# Sheet2.net
KiCad netlist of a schematic drawn in Altium Designer
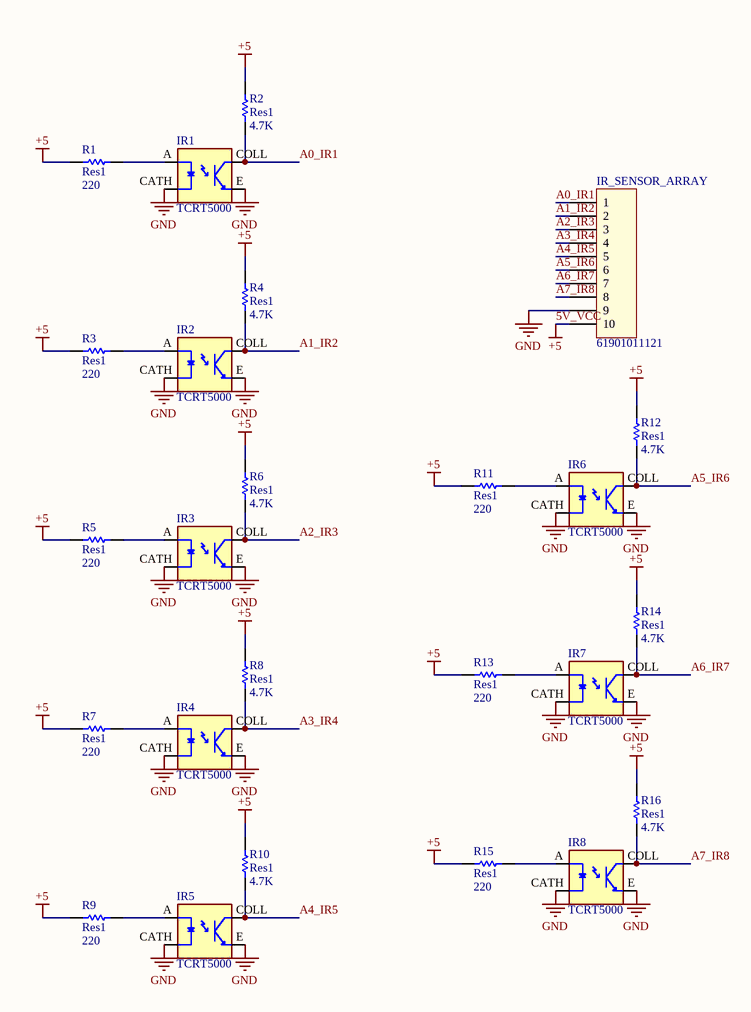
[diagram p0: Sheet2.SchDoc]

(export (version "E")
  (design (tool "Eeschema 10.0.6"))
  (components
    (comp (ref "IR1")
      (value "TCRT5000")
      (footprint "OPTO_TCRT5000")
      (description "950 nm 60 mA Through Hole Reflective Optical Sensor with Transistor Output")
      (libsource (lib "TCRT5000") (part "TCRT5000"))
    )
    (comp (ref "IR2")
      (value "TCRT5000")
      (footprint "OPTO_TCRT5000")
      (description "950 nm 60 mA Through Hole Reflective Optical Sensor with Transistor Output")
      (libsource (lib "TCRT5000") (part "TCRT5000"))
    )
    (comp (ref "IR3")
      (value "TCRT5000")
      (footprint "OPTO_TCRT5000")
      (description "950 nm 60 mA Through Hole Reflective Optical Sensor with Transistor Output")
      (libsource (lib "TCRT5000") (part "TCRT5000"))
    )
    (comp (ref "IR4")
      (value "TCRT5000")
      (footprint "OPTO_TCRT5000")
      (description "950 nm 60 mA Through Hole Reflective Optical Sensor with Transistor Output")
      (libsource (lib "TCRT5000") (part "TCRT5000"))
    )
    (comp (ref "IR5")
      (value "TCRT5000")
      (footprint "OPTO_TCRT5000")
      (description "950 nm 60 mA Through Hole Reflective Optical Sensor with Transistor Output")
      (libsource (lib "TCRT5000") (part "TCRT5000"))
    )
    (comp (ref "IR6")
      (value "TCRT5000")
      (footprint "OPTO_TCRT5000")
      (description "950 nm 60 mA Through Hole Reflective Optical Sensor with Transistor Output")
      (libsource (lib "TCRT5000") (part "TCRT5000"))
    )
    (comp (ref "IR7")
      (value "TCRT5000")
      (footprint "OPTO_TCRT5000")
      (description "950 nm 60 mA Through Hole Reflective Optical Sensor with Transistor Output")
      (libsource (lib "TCRT5000") (part "TCRT5000"))
    )
    (comp (ref "IR8")
      (value "TCRT5000")
      (footprint "OPTO_TCRT5000")
      (description "950 nm 60 mA Through Hole Reflective Optical Sensor with Transistor Output")
      (libsource (lib "TCRT5000") (part "TCRT5000"))
    )
    (comp (ref "IR_SENSOR_ARRAY")
      (value "61901011121")
      (footprint "61901011121")
      (description "WR-WTB 2.54mm Male Locking Header, 10p")
      (fields (field (name "PUBLISHER") "Wurth Elektronik"))
      (libsource (lib "Relimate") (part "61901011121"))
    )
    (comp (ref "R1")
      (value "Res1")
      (footprint "AXIAL-0.3")
      (description "Resistor")
      (fields (field (name "ALTIUM_VALUE") "220") (field (name "PUBLISHER") "Altium Limited"))
      (libsource (lib "Miscellaneous Devices") (part "Res1"))
    )
    (comp (ref "R2")
      (value "Res1")
      (footprint "AXIAL-0.3")
      (description "Resistor")
      (fields (field (name "ALTIUM_VALUE") "4.7K") (field (name "PUBLISHER") "Altium Limited"))
      (libsource (lib "Miscellaneous Devices") (part "Res1"))
    )
    (comp (ref "R3")
      (value "Res1")
      (footprint "AXIAL-0.3")
      (description "Resistor")
      (fields (field (name "ALTIUM_VALUE") "220") (field (name "PUBLISHER") "Altium Limited"))
      (libsource (lib "Miscellaneous Devices") (part "Res1"))
    )
    (comp (ref "R4")
      (value "Res1")
      (footprint "AXIAL-0.3")
      (description "Resistor")
      (fields (field (name "ALTIUM_VALUE") "4.7K") (field (name "PUBLISHER") "Altium Limited"))
      (libsource (lib "Miscellaneous Devices") (part "Res1"))
    )
    (comp (ref "R5")
      (value "Res1")
      (footprint "AXIAL-0.3")
      (description "Resistor")
      (fields (field (name "ALTIUM_VALUE") "220") (field (name "PUBLISHER") "Altium Limited"))
      (libsource (lib "Miscellaneous Devices") (part "Res1"))
    )
    (comp (ref "R6")
      (value "Res1")
      (footprint "AXIAL-0.3")
      (description "Resistor")
      (fields (field (name "ALTIUM_VALUE") "4.7K") (field (name "PUBLISHER") "Altium Limited"))
      (libsource (lib "Miscellaneous Devices") (part "Res1"))
    )
    (comp (ref "R7")
      (value "Res1")
      (footprint "AXIAL-0.3")
      (description "Resistor")
      (fields (field (name "ALTIUM_VALUE") "220") (field (name "PUBLISHER") "Altium Limited"))
      (libsource (lib "Miscellaneous Devices") (part "Res1"))
    )
    (comp (ref "R8")
      (value "Res1")
      (footprint "AXIAL-0.3")
      (description "Resistor")
      (fields (field (name "ALTIUM_VALUE") "4.7K") (field (name "PUBLISHER") "Altium Limited"))
      (libsource (lib "Miscellaneous Devices") (part "Res1"))
    )
    (comp (ref "R9")
      (value "Res1")
      (footprint "AXIAL-0.3")
      (description "Resistor")
      (fields (field (name "ALTIUM_VALUE") "220") (field (name "PUBLISHER") "Altium Limited"))
      (libsource (lib "Miscellaneous Devices") (part "Res1"))
    )
    (comp (ref "R10")
      (value "Res1")
      (footprint "AXIAL-0.3")
      (description "Resistor")
      (fields (field (name "ALTIUM_VALUE") "4.7K") (field (name "PUBLISHER") "Altium Limited"))
      (libsource (lib "Miscellaneous Devices") (part "Res1"))
    )
    (comp (ref "R11")
      (value "Res1")
      (footprint "AXIAL-0.3")
      (description "Resistor")
      (fields (field (name "ALTIUM_VALUE") "220") (field (name "PUBLISHER") "Altium Limited"))
      (libsource (lib "Miscellaneous Devices") (part "Res1"))
    )
    (comp (ref "R12")
      (value "Res1")
      (footprint "AXIAL-0.3")
      (description "Resistor")
      (fields (field (name "ALTIUM_VALUE") "4.7K") (field (name "PUBLISHER") "Altium Limited"))
      (libsource (lib "Miscellaneous Devices") (part "Res1"))
    )
    (comp (ref "R13")
      (value "Res1")
      (footprint "AXIAL-0.3")
      (description "Resistor")
      (fields (field (name "ALTIUM_VALUE") "220") (field (name "PUBLISHER") "Altium Limited"))
      (libsource (lib "Miscellaneous Devices") (part "Res1"))
    )
    (comp (ref "R14")
      (value "Res1")
      (footprint "AXIAL-0.3")
      (description "Resistor")
      (fields (field (name "ALTIUM_VALUE") "4.7K") (field (name "PUBLISHER") "Altium Limited"))
      (libsource (lib "Miscellaneous Devices") (part "Res1"))
    )
    (comp (ref "R15")
      (value "Res1")
      (footprint "AXIAL-0.3")
      (description "Resistor")
      (fields (field (name "ALTIUM_VALUE") "220") (field (name "PUBLISHER") "Altium Limited"))
      (libsource (lib "Miscellaneous Devices") (part "Res1"))
    )
    (comp (ref "R16")
      (value "Res1")
      (footprint "AXIAL-0.3")
      (description "Resistor")
      (fields (field (name "ALTIUM_VALUE") "4.7K") (field (name "PUBLISHER") "Altium Limited"))
      (libsource (lib "Miscellaneous Devices") (part "Res1"))
    )
  )
  (nets
    (net (code "1") (name "+5") (class "Default")
      (node (ref "IR_SENSOR_ARRAY") (pin "10") (pinfunction "10_10") (pintype "passive"))
      (node (ref "R1") (pin "1") (pinfunction "1_1") (pintype "passive"))
      (node (ref "R10") (pin "2") (pinfunction "2_2") (pintype "passive"))
      (node (ref "R11") (pin "1") (pinfunction "1_1") (pintype "passive"))
      (node (ref "R12") (pin "2") (pinfunction "2_2") (pintype "passive"))
      (node (ref "R13") (pin "1") (pinfunction "1_1") (pintype "passive"))
      (node (ref "R14") (pin "2") (pinfunction "2_2") (pintype "passive"))
      (node (ref "R15") (pin "1") (pinfunction "1_1") (pintype "passive"))
      (node (ref "R16") (pin "2") (pinfunction "2_2") (pintype "passive"))
      (node (ref "R2") (pin "2") (pinfunction "2_2") (pintype "passive"))
      (node (ref "R3") (pin "1") (pinfunction "1_1") (pintype "passive"))
      (node (ref "R4") (pin "2") (pinfunction "2_2") (pintype "passive"))
      (node (ref "R5") (pin "1") (pinfunction "1_1") (pintype "passive"))
      (node (ref "R6") (pin "2") (pinfunction "2_2") (pintype "passive"))
      (node (ref "R7") (pin "1") (pinfunction "1_1") (pintype "passive"))
      (node (ref "R8") (pin "2") (pinfunction "2_2") (pintype "passive"))
      (node (ref "R9") (pin "1") (pinfunction "1_1") (pintype "passive"))
    )
    (net (code "2") (name "/A0_IR1") (class "Default")
      (node (ref "IR1") (pin "COLL") (pinfunction "COLL_COLL") (pintype "passive"))
      (node (ref "IR_SENSOR_ARRAY") (pin "1") (pinfunction "1_1") (pintype "passive"))
      (node (ref "R2") (pin "1") (pinfunction "1_1") (pintype "passive"))
    )
    (net (code "3") (name "/A1_IR2") (class "Default")
      (node (ref "IR2") (pin "COLL") (pinfunction "COLL_COLL") (pintype "passive"))
      (node (ref "IR_SENSOR_ARRAY") (pin "2") (pinfunction "2_2") (pintype "passive"))
      (node (ref "R4") (pin "1") (pinfunction "1_1") (pintype "passive"))
    )
    (net (code "4") (name "/A2_IR3") (class "Default")
      (node (ref "IR3") (pin "COLL") (pinfunction "COLL_COLL") (pintype "passive"))
      (node (ref "IR_SENSOR_ARRAY") (pin "3") (pinfunction "3_3") (pintype "passive"))
      (node (ref "R6") (pin "1") (pinfunction "1_1") (pintype "passive"))
    )
    (net (code "5") (name "/A3_IR4") (class "Default")
      (node (ref "IR4") (pin "COLL") (pinfunction "COLL_COLL") (pintype "passive"))
      (node (ref "IR_SENSOR_ARRAY") (pin "4") (pinfunction "4_4") (pintype "passive"))
      (node (ref "R8") (pin "1") (pinfunction "1_1") (pintype "passive"))
    )
    (net (code "6") (name "/A4_IR5") (class "Default")
      (node (ref "IR5") (pin "COLL") (pinfunction "COLL_COLL") (pintype "passive"))
      (node (ref "IR_SENSOR_ARRAY") (pin "5") (pinfunction "5_5") (pintype "passive"))
      (node (ref "R10") (pin "1") (pinfunction "1_1") (pintype "passive"))
    )
    (net (code "7") (name "/A5_IR6") (class "Default")
      (node (ref "IR6") (pin "COLL") (pinfunction "COLL_COLL") (pintype "passive"))
      (node (ref "IR_SENSOR_ARRAY") (pin "6") (pinfunction "6_6") (pintype "passive"))
      (node (ref "R12") (pin "1") (pinfunction "1_1") (pintype "passive"))
    )
    (net (code "8") (name "/A6_IR7") (class "Default")
      (node (ref "IR7") (pin "COLL") (pinfunction "COLL_COLL") (pintype "passive"))
      (node (ref "IR_SENSOR_ARRAY") (pin "7") (pinfunction "7_7") (pintype "passive"))
      (node (ref "R14") (pin "1") (pinfunction "1_1") (pintype "passive"))
    )
    (net (code "9") (name "/A7_IR8") (class "Default")
      (node (ref "IR8") (pin "COLL") (pinfunction "COLL_COLL") (pintype "passive"))
      (node (ref "IR_SENSOR_ARRAY") (pin "8") (pinfunction "8_8") (pintype "passive"))
      (node (ref "R16") (pin "1") (pinfunction "1_1") (pintype "passive"))
    )
    (net (code "10") (name "GND") (class "Default")
      (node (ref "IR1") (pin "CATH") (pinfunction "CATH_CATH") (pintype "passive"))
      (node (ref "IR1") (pin "E") (pinfunction "E_E") (pintype "passive"))
      (node (ref "IR2") (pin "CATH") (pinfunction "CATH_CATH") (pintype "passive"))
      (node (ref "IR2") (pin "E") (pinfunction "E_E") (pintype "passive"))
      (node (ref "IR3") (pin "CATH") (pinfunction "CATH_CATH") (pintype "passive"))
      (node (ref "IR3") (pin "E") (pinfunction "E_E") (pintype "passive"))
      (node (ref "IR4") (pin "CATH") (pinfunction "CATH_CATH") (pintype "passive"))
      (node (ref "IR4") (pin "E") (pinfunction "E_E") (pintype "passive"))
      (node (ref "IR5") (pin "CATH") (pinfunction "CATH_CATH") (pintype "passive"))
      (node (ref "IR5") (pin "E") (pinfunction "E_E") (pintype "passive"))
      (node (ref "IR6") (pin "CATH") (pinfunction "CATH_CATH") (pintype "passive"))
      (node (ref "IR6") (pin "E") (pinfunction "E_E") (pintype "passive"))
      (node (ref "IR7") (pin "CATH") (pinfunction "CATH_CATH") (pintype "passive"))
      (node (ref "IR7") (pin "E") (pinfunction "E_E") (pintype "passive"))
      (node (ref "IR8") (pin "CATH") (pinfunction "CATH_CATH") (pintype "passive"))
      (node (ref "IR8") (pin "E") (pinfunction "E_E") (pintype "passive"))
      (node (ref "IR_SENSOR_ARRAY") (pin "9") (pinfunction "9_9") (pintype "passive"))
    )
    (net (code "11") (name "Net-(IR1-PadA)") (class "Default")
      (node (ref "IR1") (pin "A") (pinfunction "A_A") (pintype "passive"))
      (node (ref "R1") (pin "2") (pinfunction "2_2") (pintype "passive"))
    )
    (net (code "12") (name "Net-(IR2-PadA)") (class "Default")
      (node (ref "IR2") (pin "A") (pinfunction "A_A") (pintype "passive"))
      (node (ref "R3") (pin "2") (pinfunction "2_2") (pintype "passive"))
    )
    (net (code "13") (name "Net-(IR3-PadA)") (class "Default")
      (node (ref "IR3") (pin "A") (pinfunction "A_A") (pintype "passive"))
      (node (ref "R5") (pin "2") (pinfunction "2_2") (pintype "passive"))
    )
    (net (code "14") (name "Net-(IR4-PadA)") (class "Default")
      (node (ref "IR4") (pin "A") (pinfunction "A_A") (pintype "passive"))
      (node (ref "R7") (pin "2") (pinfunction "2_2") (pintype "passive"))
    )
    (net (code "15") (name "Net-(IR5-PadA)") (class "Default")
      (node (ref "IR5") (pin "A") (pinfunction "A_A") (pintype "passive"))
      (node (ref "R9") (pin "2") (pinfunction "2_2") (pintype "passive"))
    )
    (net (code "16") (name "Net-(IR6-PadA)") (class "Default")
      (node (ref "IR6") (pin "A") (pinfunction "A_A") (pintype "passive"))
      (node (ref "R11") (pin "2") (pinfunction "2_2") (pintype "passive"))
    )
    (net (code "17") (name "Net-(IR7-PadA)") (class "Default")
      (node (ref "IR7") (pin "A") (pinfunction "A_A") (pintype "passive"))
      (node (ref "R13") (pin "2") (pinfunction "2_2") (pintype "passive"))
    )
    (net (code "18") (name "Net-(IR8-PadA)") (class "Default")
      (node (ref "IR8") (pin "A") (pinfunction "A_A") (pintype "passive"))
      (node (ref "R15") (pin "2") (pinfunction "2_2") (pintype "passive"))
    )
  )
)
